# 2_PowerPerif.net
KiCad netlist of a schematic drawn in Altium Designer
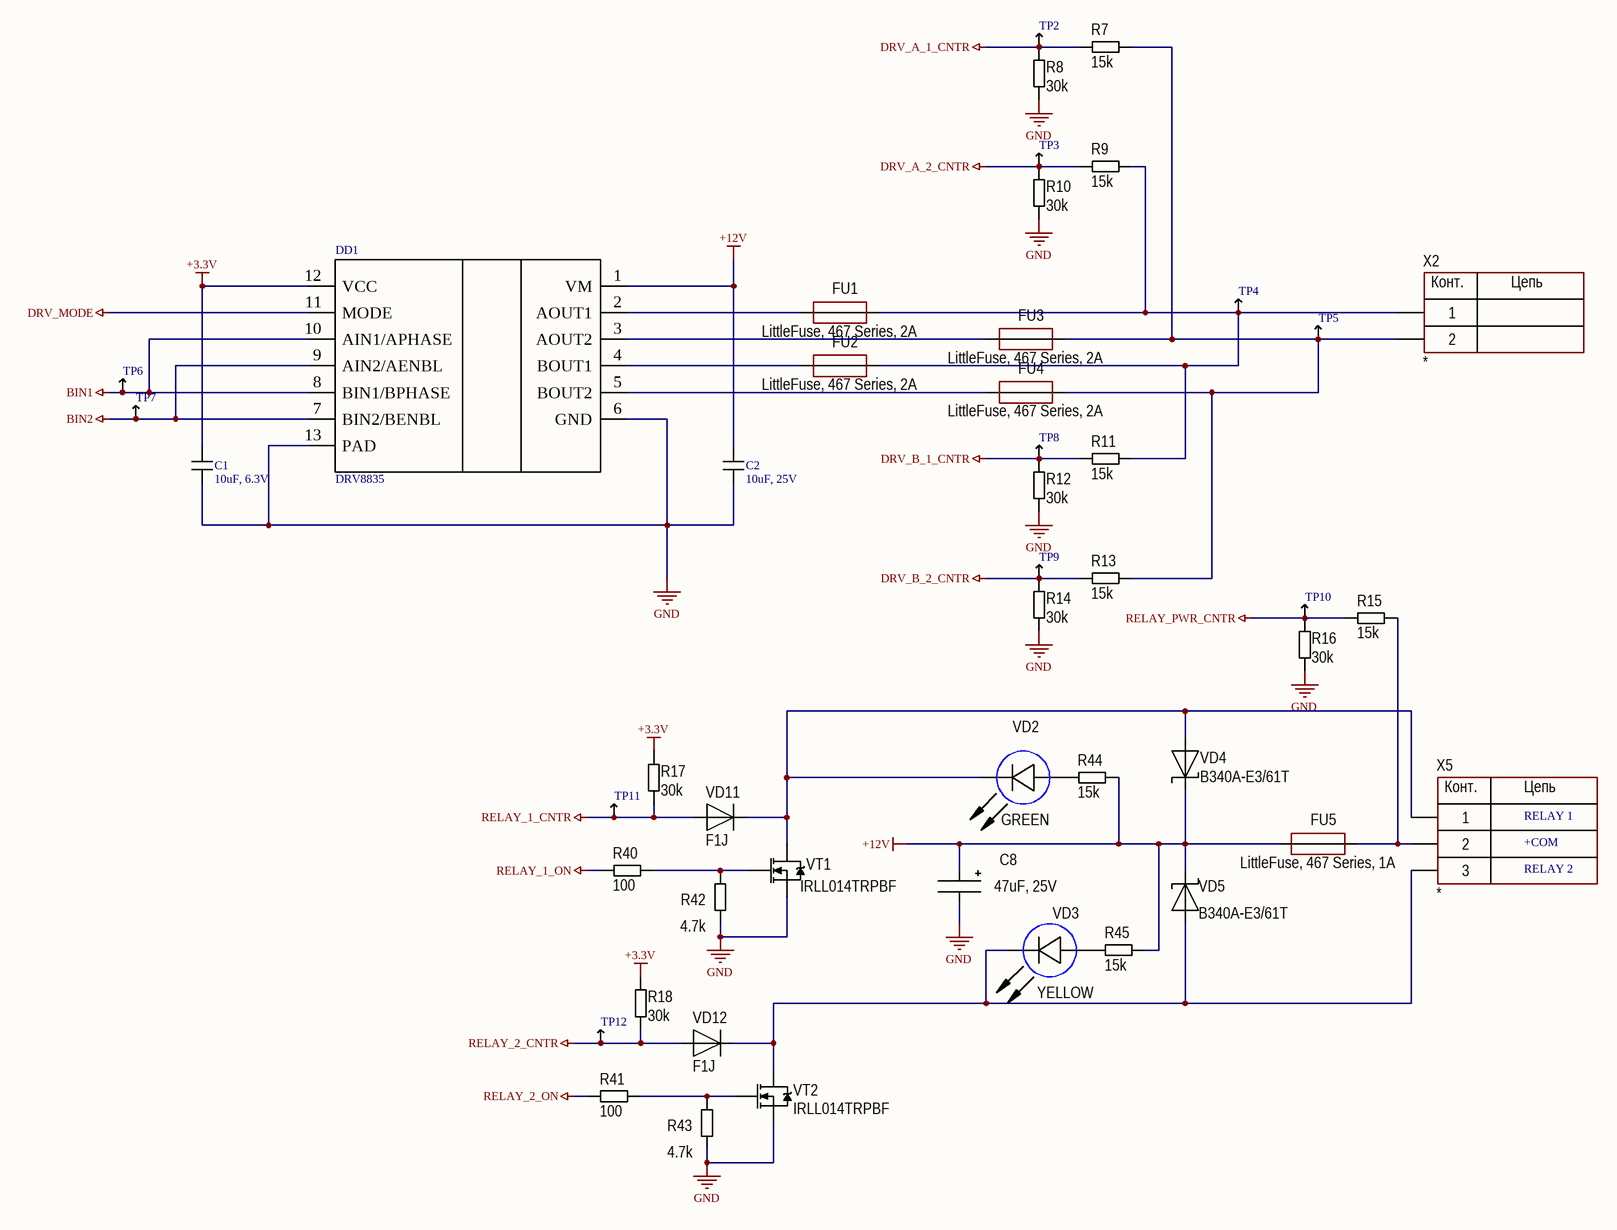
[diagram p0: 2_PowerPerif.SchDoc]

(export (version "E")
  (design (tool "Eeschema 10.0.6"))
  (components
    (comp (ref "C1")
      (value "10uF, 6.3V")
      (footprint "C_0603")
      (libsource (lib "Condensators") (part "C_SMD"))
    )
    (comp (ref "C2") (value "10uF, 25V") (footprint "C_0603") (libsource (lib "Condensators") (part "C_SMD")))
    (comp (ref "C8")
      (value "47uF, 25V")
      (footprint "D8C3.2H12")
      (libsource (lib "Condensators") (part "AlumCap"))
    )
    (comp (ref "DD1")
      (value "DRV8835")
      (footprint "WSON12")
      (description "Driver")
      (libsource (lib "MicroIC") (part "DRV8835"))
    )
    (comp (ref "FU1")
      (value "LittleFuse, 467 Series, 2A")
      (footprint "CH0603F")
      (libsource (lib "Melochi") (part "Fuse"))
    )
    (comp (ref "FU2")
      (value "LittleFuse, 467 Series, 2A")
      (footprint "CH0603F")
      (libsource (lib "Melochi") (part "Fuse"))
    )
    (comp (ref "FU3")
      (value "LittleFuse, 467 Series, 2A")
      (footprint "CH0603F")
      (libsource (lib "Melochi") (part "Fuse"))
    )
    (comp (ref "FU4")
      (value "LittleFuse, 467 Series, 2A")
      (footprint "CH0603F")
      (libsource (lib "Melochi") (part "Fuse"))
    )
    (comp (ref "FU5")
      (value "LittleFuse, 467 Series, 1A")
      (footprint "CH0603F")
      (libsource (lib "Melochi") (part "Fuse"))
    )
    (comp (ref "R7") (value "15k") (footprint "CH0805R") (libsource (lib "Resistors") (part "Resistor")))
    (comp (ref "R8") (value "30k") (footprint "CH0805R") (libsource (lib "Resistors") (part "Resistor")))
    (comp (ref "R9") (value "15k") (footprint "CH0805R") (libsource (lib "Resistors") (part "Resistor")))
    (comp (ref "R10") (value "30k") (footprint "CH0805R") (libsource (lib "Resistors") (part "Resistor")))
    (comp (ref "R11") (value "15k") (footprint "CH0805R") (libsource (lib "Resistors") (part "Resistor")))
    (comp (ref "R12") (value "30k") (footprint "CH0805R") (libsource (lib "Resistors") (part "Resistor")))
    (comp (ref "R13") (value "15k") (footprint "CH0805R") (libsource (lib "Resistors") (part "Resistor")))
    (comp (ref "R14") (value "30k") (footprint "CH0805R") (libsource (lib "Resistors") (part "Resistor")))
    (comp (ref "R15") (value "15k") (footprint "CH0805R") (libsource (lib "Resistors") (part "Resistor")))
    (comp (ref "R16") (value "30k") (footprint "CH0805R") (libsource (lib "Resistors") (part "Resistor")))
    (comp (ref "R17") (value "30k") (footprint "CH0805R") (libsource (lib "Resistors") (part "Resistor")))
    (comp (ref "R18") (value "30k") (footprint "CH0805R") (libsource (lib "Resistors") (part "Resistor")))
    (comp (ref "R40") (value "100") (footprint "CH0805R") (libsource (lib "Resistors") (part "Resistor")))
    (comp (ref "R41") (value "100") (footprint "CH0805R") (libsource (lib "Resistors") (part "Resistor")))
    (comp (ref "R42") (value "4.7k") (footprint "CH0805R") (libsource (lib "Resistors") (part "Resistor")))
    (comp (ref "R43") (value "4.7k") (footprint "CH0805R") (libsource (lib "Resistors") (part "Resistor")))
    (comp (ref "R44") (value "15k") (footprint "CH0805R") (libsource (lib "Resistors") (part "Resistor")))
    (comp (ref "R45") (value "15k") (footprint "CH0805R") (libsource (lib "Resistors") (part "Resistor")))
    (comp (ref "TP2") (value "TestPoint") (libsource (lib "BufLib") (part "TestPoint")))
    (comp (ref "TP3") (value "TestPoint") (libsource (lib "BufLib") (part "TestPoint")))
    (comp (ref "TP4") (value "TestPoint") (libsource (lib "BufLib") (part "TestPoint")))
    (comp (ref "TP5") (value "TestPoint") (libsource (lib "BufLib") (part "TestPoint")))
    (comp (ref "TP6") (value "TestPoint") (libsource (lib "BufLib") (part "TestPoint")))
    (comp (ref "TP7") (value "TestPoint") (libsource (lib "BufLib") (part "TestPoint")))
    (comp (ref "TP8") (value "TestPoint") (libsource (lib "BufLib") (part "TestPoint")))
    (comp (ref "TP9") (value "TestPoint") (libsource (lib "") (part "TestPoint_1")))
    (comp (ref "TP10") (value "TestPoint") (libsource (lib "") (part "TestPoint_1")))
    (comp (ref "TP11") (value "TestPoint") (libsource (lib "BufLib") (part "TestPoint")))
    (comp (ref "TP12") (value "TestPoint") (libsource (lib "BufLib") (part "TestPoint")))
    (comp (ref "VD2") (value "GREEN") (footprint "CH0603LB") (libsource (lib "Diods") (part "LED_1")))
    (comp (ref "VD3") (value "YELLOW") (footprint "CH0603LB") (libsource (lib "Diods") (part "LED_1")))
    (comp (ref "VD4")
      (value "B340A-E3/61T")
      (footprint "SMA")
      (libsource (lib "Diods") (part "Diod Schottky"))
    )
    (comp (ref "VD5")
      (value "B340A-E3/61T")
      (footprint "SMA")
      (libsource (lib "Diods") (part "Diod Schottky"))
    )
    (comp (ref "VD11") (value "F1J") (footprint "SOD123F") (libsource (lib "Diods") (part "Diod")))
    (comp (ref "VD12") (value "F1J") (footprint "SOD123F") (libsource (lib "Diods") (part "Diod")))
    (comp (ref "VT1")
      (value "IRLL014TRPBF")
      (footprint "SOT223")
      (description "Mosfet")
      (libsource (lib "Tranzistor") (part "N-chanel"))
    )
    (comp (ref "VT2")
      (value "IRLL014TRPBF")
      (footprint "SOT223")
      (description "Mosfet")
      (libsource (lib "Tranzistor") (part "N-chanel"))
    )
    (comp (ref "X2") (value "*") (footprint "CON: CWF-2") (libsource (lib "Connectors") (part "2-Connector")))
    (comp (ref "X5")
      (value "*")
      (footprint "CON: 300-03P-5.0")
      (libsource (lib "Connectors") (part "3-Connector"))
    )
  )
  (nets
    (net (code "1") (name "+3.3V") (class "Default")
      (node (ref "C1") (pin "2") (pinfunction "2_2") (pintype "passive"))
      (node (ref "DD1") (pin "12") (pinfunction "VCC_12") (pintype "passive"))
      (node (ref "R17") (pin "2") (pinfunction "2_2") (pintype "passive"))
      (node (ref "R18") (pin "2") (pinfunction "2_2") (pintype "passive"))
    )
    (net (code "2") (name "+12V") (class "Default")
      (node (ref "C2") (pin "2") (pinfunction "2_2") (pintype "passive"))
      (node (ref "C8") (pin "1") (pinfunction "1_1") (pintype "power_in"))
      (node (ref "DD1") (pin "1") (pinfunction "VM_1") (pintype "passive"))
      (node (ref "FU5") (pin "1") (pinfunction "1_1") (pintype "passive"))
      (node (ref "R44") (pin "2") (pinfunction "2_2") (pintype "passive"))
      (node (ref "R45") (pin "2") (pinfunction "2_2") (pintype "passive"))
      (node (ref "VD4") (pin "2") (pinfunction "2_2") (pintype "passive"))
      (node (ref "VD5") (pin "2") (pinfunction "2_2") (pintype "passive"))
    )
    (net (code "3") (name "BIN1") (class "Default")
      (node (ref "DD1") (pin "10") (pinfunction "AIN1/APHASE_10") (pintype "passive"))
      (node (ref "DD1") (pin "8") (pinfunction "BIN1/BPHASE_8") (pintype "passive"))
      (node (ref "TP6") (pin "0") (pinfunction "0_0") (pintype "passive"))
    )
    (net (code "4") (name "BIN2") (class "Default")
      (node (ref "DD1") (pin "7") (pinfunction "BIN2/BENBL_7") (pintype "passive"))
      (node (ref "DD1") (pin "9") (pinfunction "AIN2/AENBL_9") (pintype "passive"))
      (node (ref "TP7") (pin "0") (pinfunction "0_0") (pintype "passive"))
    )
    (net (code "5") (name "DRV_A_1_CNTR") (class "Default")
      (node (ref "R7") (pin "1") (pinfunction "1_1") (pintype "passive"))
      (node (ref "R8") (pin "2") (pinfunction "2_2") (pintype "passive"))
      (node (ref "TP2") (pin "0") (pinfunction "0_0") (pintype "passive"))
    )
    (net (code "6") (name "DRV_A_2_CNTR") (class "Default")
      (node (ref "R10") (pin "2") (pinfunction "2_2") (pintype "passive"))
      (node (ref "R9") (pin "1") (pinfunction "1_1") (pintype "passive"))
      (node (ref "TP3") (pin "0") (pinfunction "0_0") (pintype "passive"))
    )
    (net (code "7") (name "DRV_B_1_CNTR") (class "Default")
      (node (ref "R11") (pin "1") (pinfunction "1_1") (pintype "passive"))
      (node (ref "R12") (pin "2") (pinfunction "2_2") (pintype "passive"))
      (node (ref "TP8") (pin "0") (pinfunction "0_0") (pintype "passive"))
    )
    (net (code "8") (name "DRV_B_2_CNTR") (class "Default")
      (node (ref "R13") (pin "1") (pinfunction "1_1") (pintype "passive"))
      (node (ref "R14") (pin "2") (pinfunction "2_2") (pintype "passive"))
      (node (ref "TP9") (pin "0") (pinfunction "0_0") (pintype "passive"))
    )
    (net (code "9") (name "DRV_MODE") (class "Default")
      (node (ref "DD1") (pin "11") (pinfunction "MODE_11") (pintype "passive"))
    )
    (net (code "10") (name "GND") (class "Default")
      (node (ref "C1") (pin "1") (pinfunction "1_1") (pintype "passive"))
      (node (ref "C2") (pin "1") (pinfunction "1_1") (pintype "passive"))
      (node (ref "C8") (pin "2") (pinfunction "2_2") (pintype "power_in"))
      (node (ref "DD1") (pin "13") (pinfunction "PAD_13") (pintype "passive"))
      (node (ref "DD1") (pin "6") (pinfunction "GND_6") (pintype "passive"))
      (node (ref "R10") (pin "1") (pinfunction "1_1") (pintype "passive"))
      (node (ref "R12") (pin "1") (pinfunction "1_1") (pintype "passive"))
      (node (ref "R14") (pin "1") (pinfunction "1_1") (pintype "passive"))
      (node (ref "R16") (pin "1") (pinfunction "1_1") (pintype "passive"))
      (node (ref "R42") (pin "1") (pinfunction "1_1") (pintype "passive"))
      (node (ref "R43") (pin "1") (pinfunction "1_1") (pintype "passive"))
      (node (ref "R8") (pin "1") (pinfunction "1_1") (pintype "passive"))
      (node (ref "VT1") (pin "3") (pinfunction "S_3") (pintype "passive"))
      (node (ref "VT2") (pin "3") (pinfunction "S_3") (pintype "passive"))
    )
    (net (code "11") (name "Net-(DD1-AOUT1)") (class "Default")
      (node (ref "DD1") (pin "2") (pinfunction "AOUT1_2") (pintype "passive"))
      (node (ref "FU1") (pin "1") (pinfunction "1_1") (pintype "passive"))
    )
    (net (code "12") (name "Net-(DD1-AOUT2)") (class "Default")
      (node (ref "DD1") (pin "3") (pinfunction "AOUT2_3") (pintype "passive"))
      (node (ref "FU3") (pin "1") (pinfunction "1_1") (pintype "passive"))
    )
    (net (code "13") (name "Net-(DD1-BOUT1)") (class "Default")
      (node (ref "DD1") (pin "4") (pinfunction "BOUT1_4") (pintype "passive"))
      (node (ref "FU2") (pin "1") (pinfunction "1_1") (pintype "passive"))
    )
    (net (code "14") (name "Net-(DD1-BOUT2)") (class "Default")
      (node (ref "DD1") (pin "5") (pinfunction "BOUT2_5") (pintype "passive"))
      (node (ref "FU4") (pin "1") (pinfunction "1_1") (pintype "passive"))
    )
    (net (code "15") (name "Net-(FU1-Pad2)") (class "Default")
      (node (ref "FU1") (pin "2") (pinfunction "2_2") (pintype "passive"))
      (node (ref "FU2") (pin "2") (pinfunction "2_2") (pintype "passive"))
      (node (ref "R11") (pin "2") (pinfunction "2_2") (pintype "passive"))
      (node (ref "R9") (pin "2") (pinfunction "2_2") (pintype "passive"))
      (node (ref "TP4") (pin "0") (pinfunction "0_0") (pintype "passive"))
      (node (ref "X2") (pin "1") (pinfunction "1_1") (pintype "passive"))
    )
    (net (code "16") (name "Net-(FU3-Pad2)") (class "Default")
      (node (ref "FU3") (pin "2") (pinfunction "2_2") (pintype "passive"))
      (node (ref "FU4") (pin "2") (pinfunction "2_2") (pintype "passive"))
      (node (ref "R13") (pin "2") (pinfunction "2_2") (pintype "passive"))
      (node (ref "R7") (pin "2") (pinfunction "2_2") (pintype "passive"))
      (node (ref "TP5") (pin "0") (pinfunction "0_0") (pintype "passive"))
      (node (ref "X2") (pin "2") (pinfunction "2_2") (pintype "passive"))
    )
    (net (code "17") (name "Net-(FU5-Pad2)") (class "Default")
      (node (ref "FU5") (pin "2") (pinfunction "2_2") (pintype "passive"))
      (node (ref "R15") (pin "2") (pinfunction "2_2") (pintype "passive"))
      (node (ref "X5") (pin "2") (pinfunction "2_2") (pintype "passive"))
    )
    (net (code "18") (name "Net-(VD2-A)") (class "Default")
      (node (ref "R44") (pin "1") (pinfunction "1_1") (pintype "passive"))
      (node (ref "VD2") (pin "1") (pinfunction "A_1") (pintype "passive"))
    )
    (net (code "19") (name "Net-(VD2-C)") (class "Default")
      (node (ref "VD11") (pin "2") (pinfunction "2_2") (pintype "passive"))
      (node (ref "VD2") (pin "2") (pinfunction "C_2") (pintype "passive"))
      (node (ref "VD4") (pin "1") (pinfunction "1_1") (pintype "passive"))
      (node (ref "VT1") (pin "2") (pinfunction "D_2") (pintype "passive"))
      (node (ref "X5") (pin "1") (pinfunction "1_1") (pintype "passive"))
    )
    (net (code "20") (name "Net-(VD3-A)") (class "Default")
      (node (ref "R45") (pin "1") (pinfunction "1_1") (pintype "passive"))
      (node (ref "VD3") (pin "1") (pinfunction "A_1") (pintype "passive"))
    )
    (net (code "21") (name "Net-(VD3-C)") (class "Default")
      (node (ref "VD12") (pin "2") (pinfunction "2_2") (pintype "passive"))
      (node (ref "VD3") (pin "2") (pinfunction "C_2") (pintype "passive"))
      (node (ref "VD5") (pin "1") (pinfunction "1_1") (pintype "passive"))
      (node (ref "VT2") (pin "2") (pinfunction "D_2") (pintype "passive"))
      (node (ref "X5") (pin "3") (pinfunction "3_3") (pintype "passive"))
    )
    (net (code "22") (name "Net-(VT1-G)") (class "Default")
      (node (ref "R40") (pin "1") (pinfunction "1_1") (pintype "passive"))
      (node (ref "R42") (pin "2") (pinfunction "2_2") (pintype "passive"))
      (node (ref "VT1") (pin "1") (pinfunction "G_1") (pintype "passive"))
    )
    (net (code "23") (name "Net-(VT2-G)") (class "Default")
      (node (ref "R41") (pin "1") (pinfunction "1_1") (pintype "passive"))
      (node (ref "R43") (pin "2") (pinfunction "2_2") (pintype "passive"))
      (node (ref "VT2") (pin "1") (pinfunction "G_1") (pintype "passive"))
    )
    (net (code "24") (name "RELAY_1_CNTR") (class "Default")
      (node (ref "R17") (pin "1") (pinfunction "1_1") (pintype "passive"))
      (node (ref "TP11") (pin "0") (pinfunction "0_0") (pintype "passive"))
      (node (ref "VD11") (pin "1") (pinfunction "1_1") (pintype "passive"))
    )
    (net (code "25") (name "RELAY_1_ON") (class "Default")
      (node (ref "R40") (pin "2") (pinfunction "2_2") (pintype "passive"))
    )
    (net (code "26") (name "RELAY_2_CNTR") (class "Default")
      (node (ref "R18") (pin "1") (pinfunction "1_1") (pintype "passive"))
      (node (ref "TP12") (pin "0") (pinfunction "0_0") (pintype "passive"))
      (node (ref "VD12") (pin "1") (pinfunction "1_1") (pintype "passive"))
    )
    (net (code "27") (name "RELAY_2_ON") (class "Default")
      (node (ref "R41") (pin "2") (pinfunction "2_2") (pintype "passive"))
    )
    (net (code "28") (name "RELAY_PWR_CNTR") (class "Default")
      (node (ref "R15") (pin "1") (pinfunction "1_1") (pintype "passive"))
      (node (ref "R16") (pin "2") (pinfunction "2_2") (pintype "passive"))
      (node (ref "TP10") (pin "0") (pinfunction "0_0") (pintype "passive"))
    )
  )
)
